# MCU.net
KiCad netlist of a schematic drawn in Altium Designer
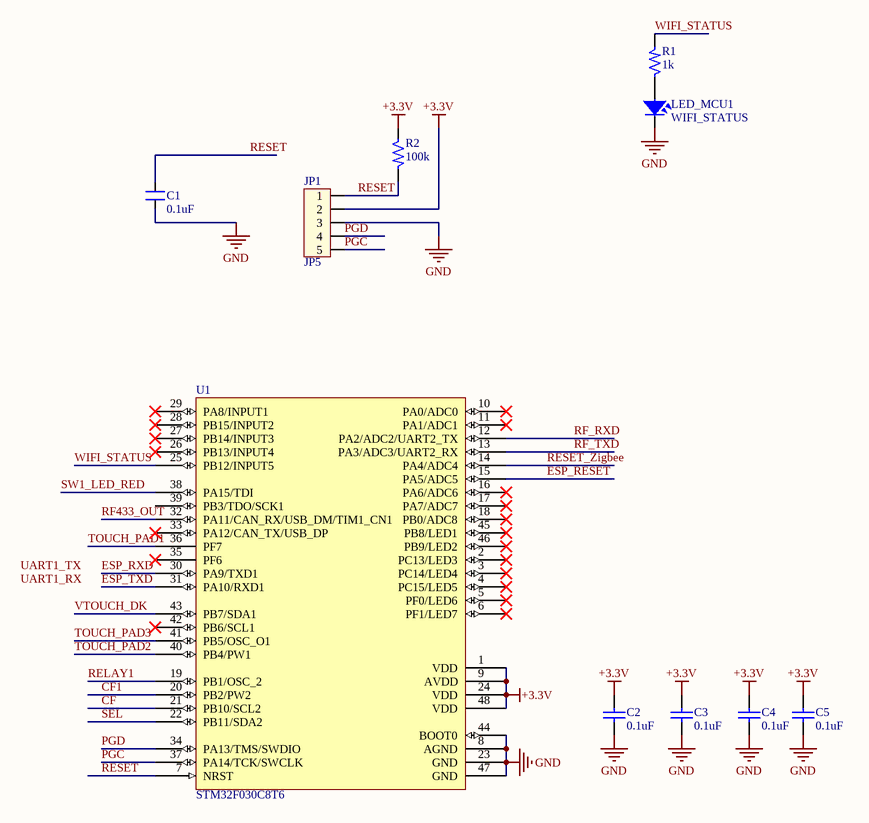
[diagram p0: MCU.SchDoc]

(export (version "E")
  (design (tool "Eeschema 10.0.6"))
  (components
    (comp (ref "C1")
      (value "0.1uF")
      (footprint "C0603")
      (description "Cremic For Xtal 1pF => 100pF")
      (libsource (lib "nl") (part "CAP"))
    )
    (comp (ref "C2")
      (value "0.1uF")
      (footprint "C0603")
      (description "Capacitor (Semiconductor SIM Model)")
      (fields (field (name "PUBLISHER") "Altium Limited"))
      (libsource (lib "VNSKILLS2014-ASM") (part "Cap Semi"))
    )
    (comp (ref "C3")
      (value "0.1uF")
      (footprint "C0603")
      (description "Capacitor (Semiconductor SIM Model)")
      (fields (field (name "PUBLISHER") "Altium Limited"))
      (libsource (lib "VNSKILLS2014-ASM") (part "Cap Semi"))
    )
    (comp (ref "C4")
      (value "0.1uF")
      (footprint "C0603")
      (description "Capacitor (Semiconductor SIM Model)")
      (fields (field (name "PUBLISHER") "Altium Limited"))
      (libsource (lib "VNSKILLS2014-ASM") (part "Cap Semi"))
    )
    (comp (ref "C5")
      (value "0.1uF")
      (footprint "C0603")
      (description "Capacitor (Semiconductor SIM Model)")
      (fields (field (name "PUBLISHER") "Altium Limited"))
      (libsource (lib "VNSKILLS2014-ASM") (part "Cap Semi"))
    )
    (comp (ref "JP1")
      (value "JP5")
      (footprint "HDR1x5")
      (description "Connector 5")
      (libsource (lib "nl") (part "Con5"))
    )
    (comp (ref "LED_MCU1")
      (value "WIFI_STATUS")
      (footprint "R0603")
      (description "LED Single colour Green and Red")
      (libsource (lib "nl") (part "LED"))
    )
    (comp (ref "R1")
      (value "1k")
      (footprint "R0603")
      (description "Resistor 1/4W")
      (libsource (lib "nl") (part "R"))
    )
    (comp (ref "R2")
      (value "100k")
      (footprint "R0603")
      (description "Resistor 1/4W")
      (libsource (lib "nl") (part "R"))
    )
    (comp (ref "U1")
      (value "STM32F030C8T6")
      (footprint "LQFP-48")
      (description "32bits STM32 48 Pins")
      (libsource (lib "Dlib") (part "STM32F103C8T6"))
    )
  )
  (nets
    (net (code "1") (name "+3.3V") (class "Default")
      (node (ref "C2") (pin "2") (pinfunction "2_2") (pintype "passive"))
      (node (ref "C3") (pin "2") (pinfunction "2_2") (pintype "passive"))
      (node (ref "C4") (pin "2") (pinfunction "2_2") (pintype "passive"))
      (node (ref "C5") (pin "2") (pinfunction "2_2") (pintype "passive"))
      (node (ref "JP1") (pin "2") (pinfunction "2_2") (pintype "passive"))
      (node (ref "R2") (pin "1") (pinfunction "1_1") (pintype "passive"))
      (node (ref "U1") (pin "1") (pinfunction "VDD_1") (pintype "power_in"))
      (node (ref "U1") (pin "24") (pinfunction "VDD_24") (pintype "power_in"))
      (node (ref "U1") (pin "48") (pinfunction "VDD_48") (pintype "power_in"))
      (node (ref "U1") (pin "9") (pinfunction "AVDD_9") (pintype "power_in"))
    )
    (net (code "2") (name "/CF") (class "Default")
      (node (ref "U1") (pin "21") (pinfunction "PB10/SCL2_21") (pintype "bidirectional"))
    )
    (net (code "3") (name "/CF1") (class "Default")
      (node (ref "U1") (pin "20") (pinfunction "PB2/PW2_20") (pintype "bidirectional"))
    )
    (net (code "4") (name "/ESP_RESET") (class "Default")
      (node (ref "U1") (pin "15") (pinfunction "PA5/ADC5_15") (pintype "bidirectional"))
    )
    (net (code "5") (name "/ESP_RXD") (class "Default")
      (node (ref "U1") (pin "30") (pinfunction "PA9/TXD1_30") (pintype "bidirectional"))
    )
    (net (code "6") (name "/ESP_TXD") (class "Default")
      (node (ref "U1") (pin "31") (pinfunction "PA10/RXD1_31") (pintype "bidirectional"))
    )
    (net (code "7") (name "/PGC") (class "Default")
      (node (ref "JP1") (pin "5") (pinfunction "5_5") (pintype "passive"))
      (node (ref "U1") (pin "37") (pinfunction "PA14/TCK/SWCLK_37") (pintype "bidirectional"))
    )
    (net (code "8") (name "/PGD") (class "Default")
      (node (ref "JP1") (pin "4") (pinfunction "4_4") (pintype "passive"))
      (node (ref "U1") (pin "34") (pinfunction "PA13/TMS/SWDIO_34") (pintype "bidirectional"))
    )
    (net (code "9") (name "/RELAY1") (class "Default")
      (node (ref "U1") (pin "19") (pinfunction "PB1/OSC_2_19") (pintype "bidirectional"))
    )
    (net (code "10") (name "/RESET") (class "Default")
      (node (ref "C1") (pin "2") (pinfunction "2_2") (pintype "passive"))
      (node (ref "JP1") (pin "1") (pinfunction "1_1") (pintype "passive"))
      (node (ref "R2") (pin "2") (pinfunction "2_2") (pintype "passive"))
      (node (ref "U1") (pin "7") (pinfunction "NRST_7") (pintype "input"))
    )
    (net (code "11") (name "/RESET_Zigbee") (class "Default")
      (node (ref "U1") (pin "14") (pinfunction "PA4/ADC4_14") (pintype "bidirectional"))
    )
    (net (code "12") (name "/RF433_OUT") (class "Default")
      (node (ref "U1") (pin "32") (pinfunction "PA11/CAN_RX/USB_DM/TIM1_CN1_32") (pintype "bidirectional"))
    )
    (net (code "13") (name "/RF_RXD") (class "Default")
      (node (ref "U1") (pin "12") (pinfunction "PA2/ADC2/UART2_TX_12") (pintype "bidirectional"))
    )
    (net (code "14") (name "/RF_TXD") (class "Default")
      (node (ref "U1") (pin "13") (pinfunction "PA3/ADC3/UART2_RX_13") (pintype "bidirectional"))
    )
    (net (code "15") (name "/SEL") (class "Default")
      (node (ref "U1") (pin "22") (pinfunction "PB11/SDA2_22") (pintype "bidirectional"))
    )
    (net (code "16") (name "/SW1_LED_RED") (class "Default")
      (node (ref "U1") (pin "38") (pinfunction "PA15/TDI_38") (pintype "bidirectional"))
    )
    (net (code "17") (name "/TOUCH_PAD1") (class "Default")
      (node (ref "U1") (pin "36") (pinfunction "PF7_36") (pintype "power_in"))
    )
    (net (code "18") (name "/TOUCH_PAD2") (class "Default")
      (node (ref "U1") (pin "40") (pinfunction "PB4/PW1_40") (pintype "bidirectional"))
    )
    (net (code "19") (name "/TOUCH_PAD3") (class "Default")
      (node (ref "U1") (pin "41") (pinfunction "PB5/OSC_O1_41") (pintype "bidirectional"))
    )
    (net (code "22") (name "/VTOUCH_DK") (class "Default")
      (node (ref "U1") (pin "43") (pinfunction "PB7/SDA1_43") (pintype "bidirectional"))
    )
    (net (code "23") (name "/WIFI_STATUS") (class "Default")
      (node (ref "R1") (pin "2") (pinfunction "2_2") (pintype "passive"))
      (node (ref "U1") (pin "25") (pinfunction "PB12/INPUT5_25") (pintype "bidirectional"))
    )
    (net (code "24") (name "GND") (class "Default")
      (node (ref "C1") (pin "1") (pinfunction "1_1") (pintype "passive"))
      (node (ref "C2") (pin "1") (pinfunction "1_1") (pintype "passive"))
      (node (ref "C3") (pin "1") (pinfunction "1_1") (pintype "passive"))
      (node (ref "C4") (pin "1") (pinfunction "1_1") (pintype "passive"))
      (node (ref "C5") (pin "1") (pinfunction "1_1") (pintype "passive"))
      (node (ref "JP1") (pin "3") (pinfunction "3_3") (pintype "passive"))
      (node (ref "LED_MCU1") (pin "2") (pinfunction "2_2") (pintype "passive"))
      (node (ref "U1") (pin "23") (pinfunction "GND_23") (pintype "power_in"))
      (node (ref "U1") (pin "44") (pinfunction "BOOT0_44") (pintype "bidirectional"))
      (node (ref "U1") (pin "47") (pinfunction "GND_47") (pintype "power_in"))
      (node (ref "U1") (pin "8") (pinfunction "AGND_8") (pintype "power_in"))
    )
    (net (code "25") (name "Net-(LED_MCU1-Pad1)") (class "Default")
      (node (ref "LED_MCU1") (pin "1") (pinfunction "1_1") (pintype "passive"))
      (node (ref "R1") (pin "1") (pinfunction "1_1") (pintype "passive"))
    )
    (net (code "26") (name "unconnected-(U1-PA0{slash}ADC0-Pad10)") (class "Default")
      (node (ref "U1") (pin "10") (pinfunction "PA0/ADC0_10") (pintype "bidirectional+no_connect"))
    )
    (net (code "27") (name "unconnected-(U1-PA1{slash}ADC1-Pad11)") (class "Default")
      (node (ref "U1") (pin "11") (pinfunction "PA1/ADC1_11") (pintype "bidirectional+no_connect"))
    )
    (net (code "28") (name "unconnected-(U1-PA6{slash}ADC6-Pad16)") (class "Default")
      (node (ref "U1") (pin "16") (pinfunction "PA6/ADC6_16") (pintype "bidirectional+no_connect"))
    )
    (net (code "29") (name "unconnected-(U1-PA7{slash}ADC7-Pad17)") (class "Default")
      (node (ref "U1") (pin "17") (pinfunction "PA7/ADC7_17") (pintype "bidirectional+no_connect"))
    )
    (net (code "30") (name "unconnected-(U1-PA8{slash}INPUT1-Pad29)") (class "Default")
      (node (ref "U1") (pin "29") (pinfunction "PA8/INPUT1_29") (pintype "bidirectional+no_connect"))
    )
    (net (code "31") (name "unconnected-(U1-PA12{slash}CAN_TX{slash}USB_DP-Pad33)") (class "Default")
      (node (ref "U1") (pin "33") (pinfunction "PA12/CAN_TX/USB_DP_33") (pintype "bidirectional+no_connect"))
    )
    (net (code "32") (name "unconnected-(U1-PB0{slash}ADC8-Pad18)") (class "Default")
      (node (ref "U1") (pin "18") (pinfunction "PB0/ADC8_18") (pintype "bidirectional+no_connect"))
    )
    (net (code "33") (name "unconnected-(U1-PB3{slash}TDO{slash}SCK1-Pad39)") (class "Default")
      (node (ref "U1") (pin "39") (pinfunction "PB3/TDO/SCK1_39") (pintype "bidirectional"))
    )
    (net (code "34") (name "unconnected-(U1-PB6{slash}SCL1-Pad42)") (class "Default")
      (node (ref "U1") (pin "42") (pinfunction "PB6/SCL1_42") (pintype "bidirectional+no_connect"))
    )
    (net (code "35") (name "unconnected-(U1-PB8{slash}LED1-Pad45)") (class "Default")
      (node (ref "U1") (pin "45") (pinfunction "PB8/LED1_45") (pintype "bidirectional+no_connect"))
    )
    (net (code "36") (name "unconnected-(U1-PB9{slash}LED2-Pad46)") (class "Default")
      (node (ref "U1") (pin "46") (pinfunction "PB9/LED2_46") (pintype "bidirectional+no_connect"))
    )
    (net (code "37") (name "unconnected-(U1-PB13{slash}INPUT4-Pad26)") (class "Default")
      (node (ref "U1") (pin "26") (pinfunction "PB13/INPUT4_26") (pintype "bidirectional+no_connect"))
    )
    (net (code "38") (name "unconnected-(U1-PB14{slash}INPUT3-Pad27)") (class "Default")
      (node (ref "U1") (pin "27") (pinfunction "PB14/INPUT3_27") (pintype "bidirectional+no_connect"))
    )
    (net (code "39") (name "unconnected-(U1-PB15{slash}INPUT2-Pad28)") (class "Default")
      (node (ref "U1") (pin "28") (pinfunction "PB15/INPUT2_28") (pintype "bidirectional+no_connect"))
    )
    (net (code "40") (name "unconnected-(U1-PC13{slash}LED3-Pad2)") (class "Default")
      (node (ref "U1") (pin "2") (pinfunction "PC13/LED3_2") (pintype "bidirectional+no_connect"))
    )
    (net (code "41") (name "unconnected-(U1-PC14{slash}LED4-Pad3)") (class "Default")
      (node (ref "U1") (pin "3") (pinfunction "PC14/LED4_3") (pintype "bidirectional+no_connect"))
    )
    (net (code "42") (name "unconnected-(U1-PC15{slash}LED5-Pad4)") (class "Default")
      (node (ref "U1") (pin "4") (pinfunction "PC15/LED5_4") (pintype "bidirectional+no_connect"))
    )
    (net (code "43") (name "unconnected-(U1-PF0{slash}LED6-Pad5)") (class "Default")
      (node (ref "U1") (pin "5") (pinfunction "PF0/LED6_5") (pintype "bidirectional+no_connect"))
    )
    (net (code "44") (name "unconnected-(U1-PF1{slash}LED7-Pad6)") (class "Default")
      (node (ref "U1") (pin "6") (pinfunction "PF1/LED7_6") (pintype "bidirectional+no_connect"))
    )
    (net (code "45") (name "unconnected-(U1-PF6-Pad35)") (class "Default")
      (node (ref "U1") (pin "35") (pinfunction "PF6_35") (pintype "power_in+no_connect"))
    )
  )
)
